# Sheet_2-copy_2024-07-28.net
KiCad netlist of a schematic drawn in Altium Designer
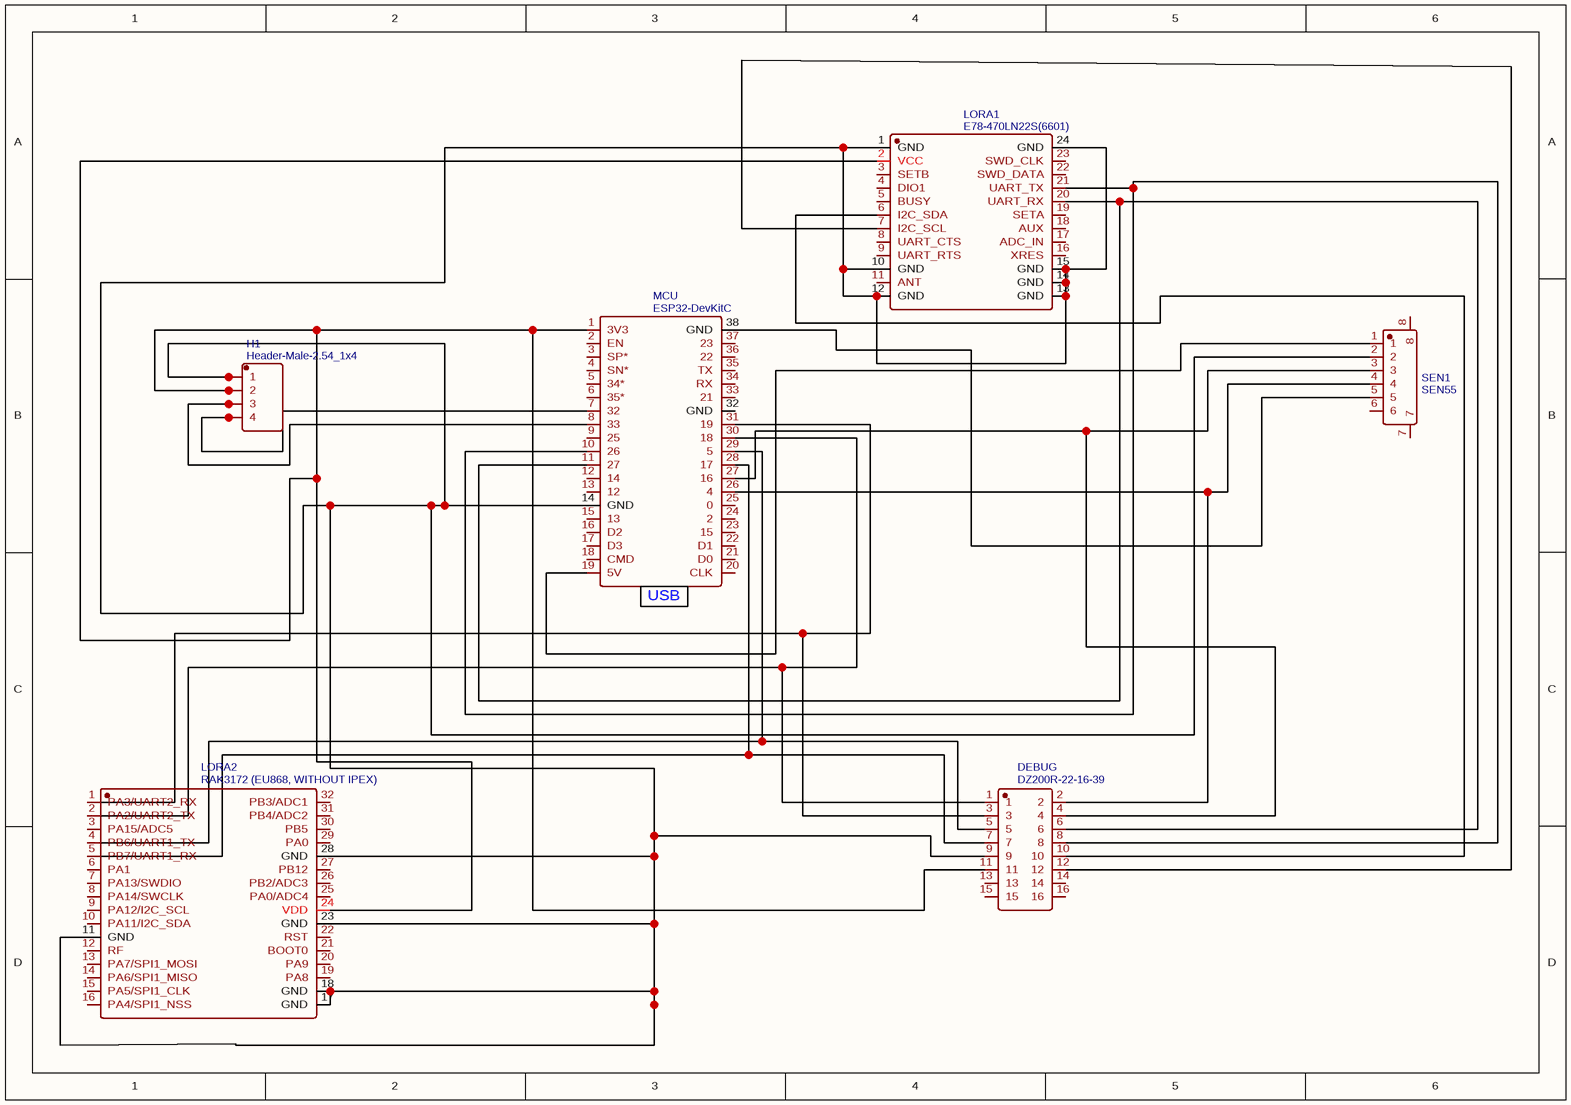
[diagram p0: Sheet_2-copy_2024-07-28.schdoc]

(export (version "E")
  (design (tool "Eeschema 10.0.6"))
  (components
    (comp (ref "DEBUG")
      (value "DZ200R-22-16-39")
      (fields (field (name "MANUFACTURER") "DEALON(德艺隆)") (field (name "CONTRIBUTOR") "LCSC"))
      (libsource (lib "altium-import") (part "root_0_DZ200R-22-16-39_"))
    )
    (comp (ref "H1")
      (value "Header-Male-2.54_1x4")
      (fields
        (field (name "MANUFACTURER") "Ckmtw(灿科盟)")
        (field (name "MANUFACTURER PART") "B-2100S04P-A110")
        (field (name "CONTRIBUTOR") "LCSC")
      )
      (libsource (lib "altium-import") (part "root_0_Header-Male-2.54_1x4_"))
    )
    (comp (ref "LORA1")
      (value "E78-470LN22S(6601)")
      (fields (field (name "MANUFACTURER") "EBYTE(亿佰特)") (field (name "CONTRIBUTOR") "LCSC"))
      (libsource (lib "altium-import") (part "root_0_E78-470LN22S(6601)_"))
    )
    (comp (ref "LORA2")
      (value "RAK3172 (EU868, WITHOUT IPEX)")
      (fields
        (field (name "MANUFACTURER PART") "RAK3172 (EU868, without IPEX)")
        (field (name "CONTRIBUTOR") "lcsc")
      )
      (libsource (lib "altium-import") (part "root_0_RAK3172 (EU868, WITHOUT IPEX)_"))
    )
    (comp (ref "MCU")
      (value "ESP32-DevKitC")
      (fields (field (name "MANUFACTURER") "32U WROOM") (field (name "CONTRIBUTOR") "Johanvd"))
      (libsource (lib "altium-import") (part "root_0_ESP32-DevKitC_"))
    )
    (comp (ref "SEN1")
      (value "SEN55")
      (fields
        (field (name "MANUFACTURER") "MOLEX")
        (field (name "MANUFACTURER PART") "532610671")
        (field (name "CONTRIBUTOR") "LCSC")
      )
      (libsource (lib "altium-import") (part "root_0_SEN55_"))
    )
  )
  (nets
    (net (code "1") (name "Net-(DEBUG-Pad9)") (class "Default")
      (node (ref "DEBUG") (pin "9") (pinfunction "9_9") (pintype "passive"))
      (node (ref "H1") (pin "1") (pinfunction "1_1") (pintype "passive"))
      (node (ref "LORA1") (pin "1") (pinfunction "GND_1") (pintype "passive"))
      (node (ref "LORA1") (pin "10") (pinfunction "GND_10") (pintype "passive"))
      (node (ref "LORA1") (pin "12") (pinfunction "GND_12") (pintype "passive"))
      (node (ref "LORA1") (pin "13") (pinfunction "GND_13") (pintype "passive"))
      (node (ref "LORA1") (pin "14") (pinfunction "GND_14") (pintype "passive"))
      (node (ref "LORA1") (pin "15") (pinfunction "GND_15") (pintype "passive"))
      (node (ref "LORA1") (pin "24") (pinfunction "GND_24") (pintype "passive"))
      (node (ref "LORA2") (pin "11") (pinfunction "GND_11") (pintype "passive"))
      (node (ref "LORA2") (pin "17") (pinfunction "GND_17") (pintype "passive"))
      (node (ref "LORA2") (pin "18") (pinfunction "GND_18") (pintype "passive"))
      (node (ref "LORA2") (pin "23") (pinfunction "GND_23") (pintype "passive"))
      (node (ref "LORA2") (pin "28") (pinfunction "GND_28") (pintype "passive"))
      (node (ref "MCU") (pin "14") (pinfunction "GND_14") (pintype "passive"))
      (node (ref "SEN1") (pin "2") (pinfunction "2_2") (pintype "passive"))
    )
    (net (code "2") (name "Net-(LORA1-I2C_SCL)") (class "Default")
      (node (ref "DEBUG") (pin "12") (pinfunction "12_12") (pintype "passive"))
      (node (ref "LORA1") (pin "7") (pinfunction "I2C_SCL_7") (pintype "passive"))
    )
    (net (code "3") (name "Net-(LORA1-I2C_SDA)") (class "Default")
      (node (ref "DEBUG") (pin "10") (pinfunction "10_10") (pintype "passive"))
      (node (ref "LORA1") (pin "6") (pinfunction "I2C_SDA_6") (pintype "passive"))
    )
    (net (code "4") (name "Net-(LORA1-UART_RX)") (class "Default")
      (node (ref "DEBUG") (pin "6") (pinfunction "6_6") (pintype "passive"))
      (node (ref "LORA1") (pin "20") (pinfunction "UART_RX_20") (pintype "passive"))
      (node (ref "MCU") (pin "11") (pinfunction "27_11") (pintype "passive"))
    )
    (net (code "5") (name "Net-(LORA1-UART_TX)") (class "Default")
      (node (ref "DEBUG") (pin "8") (pinfunction "8_8") (pintype "passive"))
      (node (ref "LORA1") (pin "21") (pinfunction "UART_TX_21") (pintype "passive"))
      (node (ref "MCU") (pin "10") (pinfunction "26_10") (pintype "passive"))
    )
    (net (code "6") (name "Net-(LORA1-VCC)") (class "Default")
      (node (ref "DEBUG") (pin "11") (pinfunction "11_11") (pintype "passive"))
      (node (ref "H1") (pin "2") (pinfunction "2_2") (pintype "passive"))
      (node (ref "LORA1") (pin "2") (pinfunction "VCC_2") (pintype "passive"))
      (node (ref "LORA2") (pin "24") (pinfunction "VDD_24") (pintype "passive"))
      (node (ref "MCU") (pin "1") (pinfunction "3V3_1") (pintype "passive"))
    )
    (net (code "7") (name "Net-(LORA2-PA2{slash}UART2_TX)") (class "Default")
      (node (ref "DEBUG") (pin "1") (pinfunction "1_1") (pintype "passive"))
      (node (ref "LORA2") (pin "2") (pinfunction "PA2/UART2_TX_2") (pintype "passive"))
      (node (ref "MCU") (pin "30") (pinfunction "18_30") (pintype "passive"))
    )
    (net (code "8") (name "Net-(LORA2-PA3{slash}UART2_RX)") (class "Default")
      (node (ref "DEBUG") (pin "3") (pinfunction "3_3") (pintype "passive"))
      (node (ref "LORA2") (pin "1") (pinfunction "PA3/UART2_RX_1") (pintype "passive"))
      (node (ref "MCU") (pin "31") (pinfunction "19_31") (pintype "passive"))
    )
    (net (code "9") (name "Net-(LORA2-PB6{slash}UART1_TX)") (class "Default")
      (node (ref "DEBUG") (pin "5") (pinfunction "5_5") (pintype "passive"))
      (node (ref "LORA2") (pin "4") (pinfunction "PB6/UART1_TX_4") (pintype "passive"))
      (node (ref "MCU") (pin "29") (pinfunction "5_29") (pintype "passive"))
    )
    (net (code "10") (name "Net-(LORA2-PB7{slash}UART1_RX)") (class "Default")
      (node (ref "DEBUG") (pin "7") (pinfunction "7_7") (pintype "passive"))
      (node (ref "LORA2") (pin "5") (pinfunction "PB7/UART1_RX_5") (pintype "passive"))
      (node (ref "MCU") (pin "28") (pinfunction "17_28") (pintype "passive"))
    )
    (net (code "11") (name "Net-(MCU-4)") (class "Default")
      (node (ref "DEBUG") (pin "2") (pinfunction "2_2") (pintype "passive"))
      (node (ref "MCU") (pin "26") (pinfunction "4_26") (pintype "passive"))
      (node (ref "SEN1") (pin "4") (pinfunction "4_4") (pintype "passive"))
    )
    (net (code "12") (name "Net-(MCU-5V)") (class "Default")
      (node (ref "MCU") (pin "19") (pinfunction "5V_19") (pintype "passive"))
      (node (ref "SEN1") (pin "1") (pinfunction "1_1") (pintype "passive"))
    )
    (net (code "13") (name "Net-(MCU-16)") (class "Default")
      (node (ref "DEBUG") (pin "4") (pinfunction "4_4") (pintype "passive"))
      (node (ref "MCU") (pin "27") (pinfunction "16_27") (pintype "passive"))
      (node (ref "SEN1") (pin "3") (pinfunction "3_3") (pintype "passive"))
    )
    (net (code "14") (name "Net-(MCU-32)") (class "Default")
      (node (ref "H1") (pin "4") (pinfunction "4_4") (pintype "passive"))
      (node (ref "MCU") (pin "7") (pinfunction "32_7") (pintype "passive"))
    )
    (net (code "15") (name "Net-(MCU-33)") (class "Default")
      (node (ref "H1") (pin "3") (pinfunction "3_3") (pintype "passive"))
      (node (ref "MCU") (pin "8") (pinfunction "33_8") (pintype "passive"))
    )
    (net (code "16") (name "Net-(MCU-GND-Pad38)") (class "Default")
      (node (ref "MCU") (pin "38") (pinfunction "GND_38") (pintype "passive"))
      (node (ref "SEN1") (pin "5") (pinfunction "5_5") (pintype "passive"))
    )
    (net (code "17") (name "unconnected-(DEBUG-Pad13)") (class "Default")
      (node (ref "DEBUG") (pin "13") (pinfunction "13_13") (pintype "passive"))
    )
    (net (code "18") (name "unconnected-(DEBUG-Pad14)") (class "Default")
      (node (ref "DEBUG") (pin "14") (pinfunction "14_14") (pintype "passive"))
    )
    (net (code "19") (name "unconnected-(DEBUG-Pad15)") (class "Default")
      (node (ref "DEBUG") (pin "15") (pinfunction "15_15") (pintype "passive"))
    )
    (net (code "20") (name "unconnected-(DEBUG-Pad16)") (class "Default")
      (node (ref "DEBUG") (pin "16") (pinfunction "16_16") (pintype "passive"))
    )
    (net (code "21") (name "unconnected-(LORA1-ADC_IN-Pad17)") (class "Default")
      (node (ref "LORA1") (pin "17") (pinfunction "ADC_IN_17") (pintype "passive"))
    )
    (net (code "22") (name "unconnected-(LORA1-ANT-Pad11)") (class "Default")
      (node (ref "LORA1") (pin "11") (pinfunction "ANT_11") (pintype "passive"))
    )
    (net (code "23") (name "unconnected-(LORA1-AUX-Pad18)") (class "Default")
      (node (ref "LORA1") (pin "18") (pinfunction "AUX_18") (pintype "passive"))
    )
    (net (code "24") (name "unconnected-(LORA1-BUSY-Pad5)") (class "Default")
      (node (ref "LORA1") (pin "5") (pinfunction "BUSY_5") (pintype "passive"))
    )
    (net (code "25") (name "unconnected-(LORA1-DIO1-Pad4)") (class "Default")
      (node (ref "LORA1") (pin "4") (pinfunction "DIO1_4") (pintype "passive"))
    )
    (net (code "26") (name "unconnected-(LORA1-SETA-Pad19)") (class "Default")
      (node (ref "LORA1") (pin "19") (pinfunction "SETA_19") (pintype "passive"))
    )
    (net (code "27") (name "unconnected-(LORA1-SETB-Pad3)") (class "Default")
      (node (ref "LORA1") (pin "3") (pinfunction "SETB_3") (pintype "passive"))
    )
    (net (code "28") (name "unconnected-(LORA1-SWD_CLK-Pad23)") (class "Default")
      (node (ref "LORA1") (pin "23") (pinfunction "SWD_CLK_23") (pintype "passive"))
    )
    (net (code "29") (name "unconnected-(LORA1-SWD_DATA-Pad22)") (class "Default")
      (node (ref "LORA1") (pin "22") (pinfunction "SWD_DATA_22") (pintype "passive"))
    )
    (net (code "30") (name "unconnected-(LORA1-UART_CTS-Pad8)") (class "Default")
      (node (ref "LORA1") (pin "8") (pinfunction "UART_CTS_8") (pintype "passive"))
    )
    (net (code "31") (name "unconnected-(LORA1-UART_RTS-Pad9)") (class "Default")
      (node (ref "LORA1") (pin "9") (pinfunction "UART_RTS_9") (pintype "passive"))
    )
    (net (code "32") (name "unconnected-(LORA1-XRES-Pad16)") (class "Default")
      (node (ref "LORA1") (pin "16") (pinfunction "XRES_16") (pintype "passive"))
    )
    (net (code "33") (name "unconnected-(LORA2-BOOT0-Pad21)") (class "Default")
      (node (ref "LORA2") (pin "21") (pinfunction "BOOT0_21") (pintype "passive"))
    )
    (net (code "34") (name "unconnected-(LORA2-PA0-Pad29)") (class "Default")
      (node (ref "LORA2") (pin "29") (pinfunction "PA0_29") (pintype "passive"))
    )
    (net (code "35") (name "unconnected-(LORA2-PA0{slash}ADC4-Pad25)") (class "Default")
      (node (ref "LORA2") (pin "25") (pinfunction "PA0/ADC4_25") (pintype "passive"))
    )
    (net (code "36") (name "unconnected-(LORA2-PA1-Pad6)") (class "Default")
      (node (ref "LORA2") (pin "6") (pinfunction "PA1_6") (pintype "passive"))
    )
    (net (code "37") (name "unconnected-(LORA2-PA4{slash}SPI1_NSS-Pad16)") (class "Default")
      (node (ref "LORA2") (pin "16") (pinfunction "PA4/SPI1_NSS_16") (pintype "passive"))
    )
    (net (code "38") (name "unconnected-(LORA2-PA5{slash}SPI1_CLK-Pad15)") (class "Default")
      (node (ref "LORA2") (pin "15") (pinfunction "PA5/SPI1_CLK_15") (pintype "passive"))
    )
    (net (code "39") (name "unconnected-(LORA2-PA6{slash}SPI1_MISO-Pad14)") (class "Default")
      (node (ref "LORA2") (pin "14") (pinfunction "PA6/SPI1_MISO_14") (pintype "passive"))
    )
    (net (code "40") (name "unconnected-(LORA2-PA7{slash}SPI1_MOSI-Pad13)") (class "Default")
      (node (ref "LORA2") (pin "13") (pinfunction "PA7/SPI1_MOSI_13") (pintype "passive"))
    )
    (net (code "41") (name "unconnected-(LORA2-PA8-Pad19)") (class "Default")
      (node (ref "LORA2") (pin "19") (pinfunction "PA8_19") (pintype "passive"))
    )
    (net (code "42") (name "unconnected-(LORA2-PA9-Pad20)") (class "Default")
      (node (ref "LORA2") (pin "20") (pinfunction "PA9_20") (pintype "passive"))
    )
    (net (code "43") (name "unconnected-(LORA2-PA11{slash}I2C_SDA-Pad10)") (class "Default")
      (node (ref "LORA2") (pin "10") (pinfunction "PA11/I2C_SDA_10") (pintype "passive"))
    )
    (net (code "44") (name "unconnected-(LORA2-PA12{slash}I2C_SCL-Pad9)") (class "Default")
      (node (ref "LORA2") (pin "9") (pinfunction "PA12/I2C_SCL_9") (pintype "passive"))
    )
    (net (code "45") (name "unconnected-(LORA2-PA13{slash}SWDIO-Pad7)") (class "Default")
      (node (ref "LORA2") (pin "7") (pinfunction "PA13/SWDIO_7") (pintype "passive"))
    )
    (net (code "46") (name "unconnected-(LORA2-PA14{slash}SWCLK-Pad8)") (class "Default")
      (node (ref "LORA2") (pin "8") (pinfunction "PA14/SWCLK_8") (pintype "passive"))
    )
    (net (code "47") (name "unconnected-(LORA2-PA15{slash}ADC5-Pad3)") (class "Default")
      (node (ref "LORA2") (pin "3") (pinfunction "PA15/ADC5_3") (pintype "passive"))
    )
    (net (code "48") (name "unconnected-(LORA2-PB2{slash}ADC3-Pad26)") (class "Default")
      (node (ref "LORA2") (pin "26") (pinfunction "PB2/ADC3_26") (pintype "passive"))
    )
    (net (code "49") (name "unconnected-(LORA2-PB3{slash}ADC1-Pad32)") (class "Default")
      (node (ref "LORA2") (pin "32") (pinfunction "PB3/ADC1_32") (pintype "passive"))
    )
    (net (code "50") (name "unconnected-(LORA2-PB4{slash}ADC2-Pad31)") (class "Default")
      (node (ref "LORA2") (pin "31") (pinfunction "PB4/ADC2_31") (pintype "passive"))
    )
    (net (code "51") (name "unconnected-(LORA2-PB5-Pad30)") (class "Default")
      (node (ref "LORA2") (pin "30") (pinfunction "PB5_30") (pintype "passive"))
    )
    (net (code "52") (name "unconnected-(LORA2-PB12-Pad27)") (class "Default")
      (node (ref "LORA2") (pin "27") (pinfunction "PB12_27") (pintype "passive"))
    )
    (net (code "53") (name "unconnected-(LORA2-RF-Pad12)") (class "Default")
      (node (ref "LORA2") (pin "12") (pinfunction "RF_12") (pintype "passive"))
    )
    (net (code "54") (name "unconnected-(LORA2-RST-Pad22)") (class "Default")
      (node (ref "LORA2") (pin "22") (pinfunction "RST_22") (pintype "passive"))
    )
    (net (code "55") (name "unconnected-(MCU-0-Pad25)") (class "Default")
      (node (ref "MCU") (pin "25") (pinfunction "0_25") (pintype "passive"))
    )
    (net (code "56") (name "unconnected-(MCU-2-Pad24)") (class "Default")
      (node (ref "MCU") (pin "24") (pinfunction "2_24") (pintype "passive"))
    )
    (net (code "57") (name "unconnected-(MCU-12-Pad13)") (class "Default")
      (node (ref "MCU") (pin "13") (pinfunction "12_13") (pintype "passive"))
    )
    (net (code "58") (name "unconnected-(MCU-13-Pad15)") (class "Default")
      (node (ref "MCU") (pin "15") (pinfunction "13_15") (pintype "passive"))
    )
    (net (code "59") (name "unconnected-(MCU-14-Pad12)") (class "Default")
      (node (ref "MCU") (pin "12") (pinfunction "14_12") (pintype "passive"))
    )
    (net (code "60") (name "unconnected-(MCU-15-Pad23)") (class "Default")
      (node (ref "MCU") (pin "23") (pinfunction "15_23") (pintype "passive"))
    )
    (net (code "61") (name "unconnected-(MCU-21-Pad33)") (class "Default")
      (node (ref "MCU") (pin "33") (pinfunction "21_33") (pintype "passive"))
    )
    (net (code "62") (name "unconnected-(MCU-22-Pad36)") (class "Default")
      (node (ref "MCU") (pin "36") (pinfunction "22_36") (pintype "passive"))
    )
    (net (code "63") (name "unconnected-(MCU-23-Pad37)") (class "Default")
      (node (ref "MCU") (pin "37") (pinfunction "23_37") (pintype "passive"))
    )
    (net (code "64") (name "unconnected-(MCU-25-Pad9)") (class "Default")
      (node (ref "MCU") (pin "9") (pinfunction "25_9") (pintype "passive"))
    )
    (net (code "65") (name "unconnected-(MCU-34*-Pad5)") (class "Default")
      (node (ref "MCU") (pin "5") (pinfunction "34*_5") (pintype "passive"))
    )
    (net (code "66") (name "unconnected-(MCU-35*-Pad6)") (class "Default")
      (node (ref "MCU") (pin "6") (pinfunction "35*_6") (pintype "passive"))
    )
    (net (code "67") (name "unconnected-(MCU-CLK-Pad20)") (class "Default")
      (node (ref "MCU") (pin "20") (pinfunction "CLK_20") (pintype "passive"))
    )
    (net (code "68") (name "unconnected-(MCU-CMD-Pad18)") (class "Default")
      (node (ref "MCU") (pin "18") (pinfunction "CMD_18") (pintype "passive"))
    )
    (net (code "69") (name "unconnected-(MCU-D0-Pad21)") (class "Default")
      (node (ref "MCU") (pin "21") (pinfunction "D0_21") (pintype "passive"))
    )
    (net (code "70") (name "unconnected-(MCU-D1-Pad22)") (class "Default")
      (node (ref "MCU") (pin "22") (pinfunction "D1_22") (pintype "passive"))
    )
    (net (code "71") (name "unconnected-(MCU-D2-Pad16)") (class "Default")
      (node (ref "MCU") (pin "16") (pinfunction "D2_16") (pintype "passive"))
    )
    (net (code "72") (name "unconnected-(MCU-D3-Pad17)") (class "Default")
      (node (ref "MCU") (pin "17") (pinfunction "D3_17") (pintype "passive"))
    )
    (net (code "73") (name "unconnected-(MCU-EN-Pad2)") (class "Default")
      (node (ref "MCU") (pin "2") (pinfunction "EN_2") (pintype "passive"))
    )
    (net (code "74") (name "unconnected-(MCU-GND-Pad32)") (class "Default")
      (node (ref "MCU") (pin "32") (pinfunction "GND_32") (pintype "passive"))
    )
    (net (code "75") (name "unconnected-(MCU-RX-Pad34)") (class "Default")
      (node (ref "MCU") (pin "34") (pinfunction "RX_34") (pintype "passive"))
    )
    (net (code "76") (name "unconnected-(MCU-SN*-Pad4)") (class "Default")
      (node (ref "MCU") (pin "4") (pinfunction "SN*_4") (pintype "passive"))
    )
    (net (code "77") (name "unconnected-(MCU-SP*-Pad3)") (class "Default")
      (node (ref "MCU") (pin "3") (pinfunction "SP*_3") (pintype "passive"))
    )
    (net (code "78") (name "unconnected-(MCU-TX-Pad35)") (class "Default")
      (node (ref "MCU") (pin "35") (pinfunction "TX_35") (pintype "passive"))
    )
    (net (code "79") (name "unconnected-(SEN1-Pad6)") (class "Default")
      (node (ref "SEN1") (pin "6") (pinfunction "6_6") (pintype "passive"))
    )
    (net (code "80") (name "unconnected-(SEN1-Pad7)") (class "Default")
      (node (ref "SEN1") (pin "7") (pinfunction "7_7") (pintype "passive"))
    )
    (net (code "81") (name "unconnected-(SEN1-Pad8)") (class "Default")
      (node (ref "SEN1") (pin "8") (pinfunction "8_8") (pintype "passive"))
    )
  )
)
